# Power_Supply.net
KiCad netlist of a schematic drawn in Altium Designer
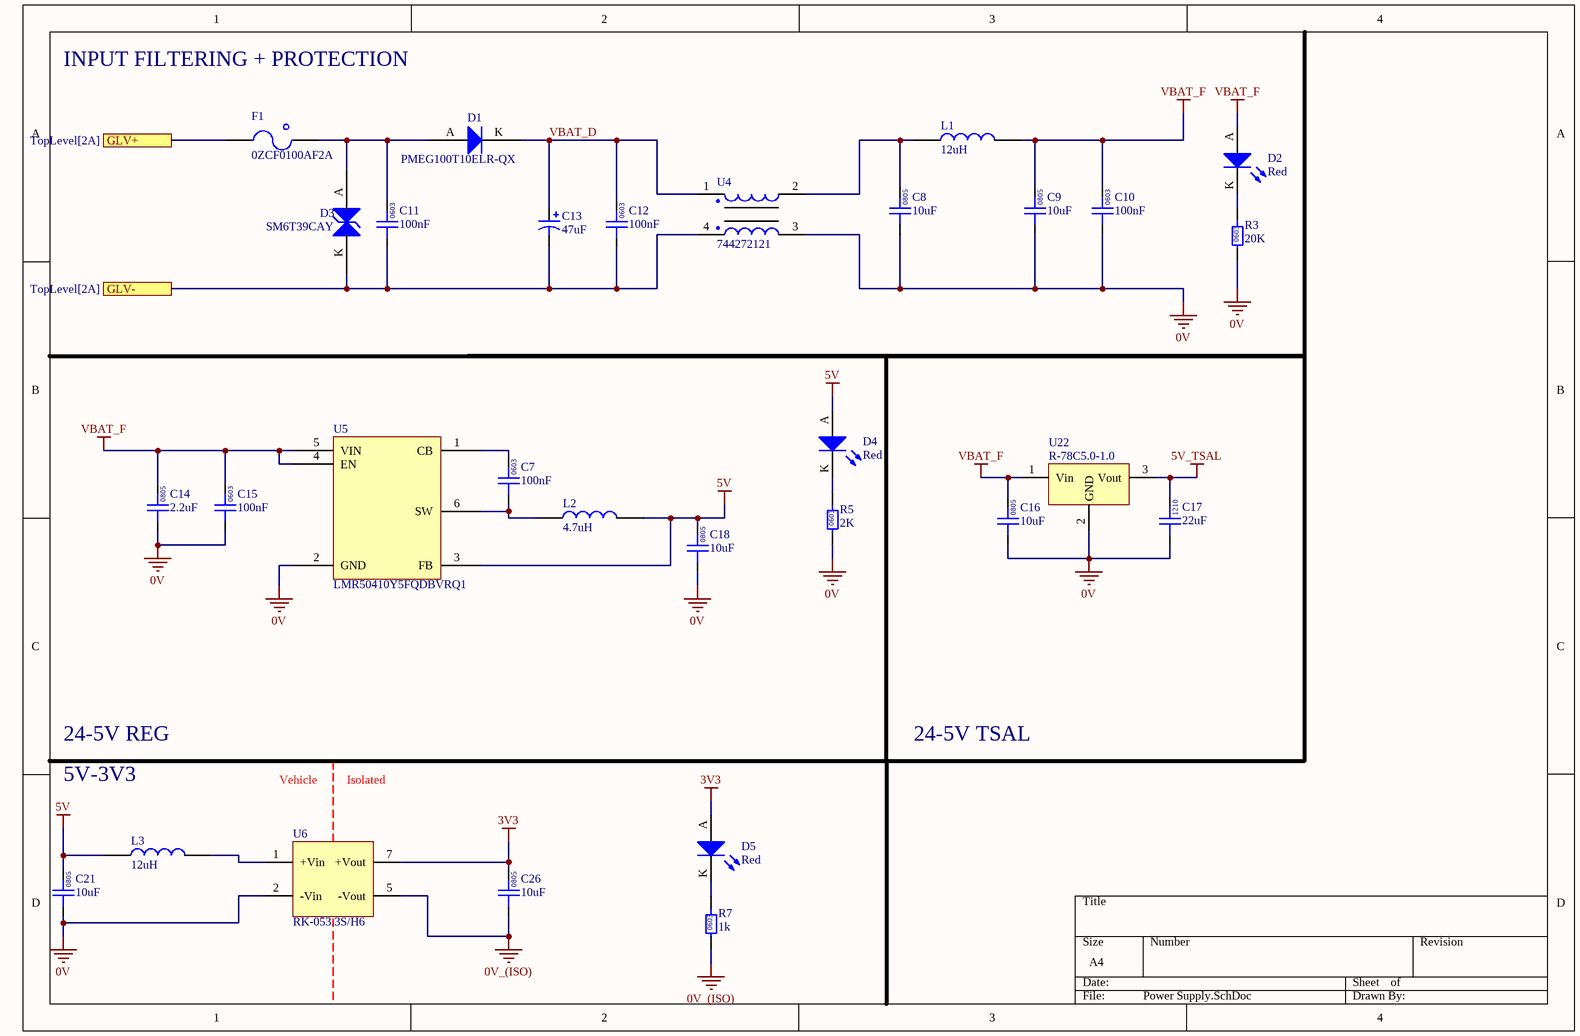
[diagram p0: Power Supply.SchDoc]

(export (version "E")
  (design (tool "Eeschema 10.0.6"))
  (components
    (comp (ref "C7")
      (value "100nF")
      (footprint "0603")
      (fields
        (field (name "PART NUMBER") "GCM188L81H104KA57D")
        (field (name "MANUFACTURER") "muRata")
        (field (name "TOLERANCE") "±10%")
      )
      (libsource (lib "ts_standard_library") (part "Capacitor 0603"))
    )
    (comp (ref "C8")
      (value "10uF")
      (footprint "0805")
      (fields
        (field (name "PART NUMBER") "GRM21BR6YA106KE43L")
        (field (name "MANUFACTURER") "muRata")
        (field (name "TOLERANCE") "10%")
      )
      (libsource (lib "ts_standard_library") (part "Capacitor 0805"))
    )
    (comp (ref "C9")
      (value "10uF")
      (footprint "0805")
      (fields
        (field (name "PART NUMBER") "GRM21BR6YA106KE43L")
        (field (name "MANUFACTURER") "muRata")
        (field (name "TOLERANCE") "10%")
      )
      (libsource (lib "ts_standard_library") (part "Capacitor 0805"))
    )
    (comp (ref "C10")
      (value "100nF")
      (footprint "0603")
      (fields
        (field (name "PART NUMBER") "GCM188L81H104KA57D")
        (field (name "MANUFACTURER") "muRata")
        (field (name "TOLERANCE") "±10%")
      )
      (libsource (lib "ts_standard_library") (part "Capacitor 0603"))
    )
    (comp (ref "C11")
      (value "100nF")
      (footprint "0603")
      (fields
        (field (name "PART NUMBER") "GCM188L81H104KA57D")
        (field (name "MANUFACTURER") "muRata")
        (field (name "TOLERANCE") "±10%")
      )
      (libsource (lib "ts_standard_library") (part "Capacitor 0603"))
    )
    (comp (ref "C12")
      (value "100nF")
      (footprint "0603")
      (fields
        (field (name "PART NUMBER") "GCM188L81H104KA57D")
        (field (name "MANUFACTURER") "muRata")
        (field (name "TOLERANCE") "±10%")
      )
      (libsource (lib "ts_standard_library") (part "Capacitor 0603"))
    )
    (comp (ref "C13")
      (value "47uF")
      (footprint "CHEMI-CON ELCO")
      (fields (field (name "PART NUMBER") "HHXA350ARA470MF61G"))
      (libsource (lib "ts_standard_library") (part "Capacitor (Polarised)"))
    )
    (comp (ref "C14")
      (value "2.2uF")
      (footprint "0805")
      (fields
        (field (name "PART NUMBER") "GRM21BR61A226ME51L")
        (field (name "MANUFACTURER") "muRata")
        (field (name "TOLERANCE") "20%")
      )
      (libsource (lib "ts_standard_library") (part "Capacitor 0805"))
    )
    (comp (ref "C15")
      (value "100nF")
      (footprint "0603")
      (fields
        (field (name "PART NUMBER") "GCM188L81H104KA57D")
        (field (name "MANUFACTURER") "muRata")
        (field (name "TOLERANCE") "±10%")
      )
      (libsource (lib "ts_standard_library") (part "Capacitor 0603"))
    )
    (comp (ref "C16")
      (value "10uF")
      (footprint "0805")
      (fields
        (field (name "PART NUMBER") "GRM21BR6YA106KE43L")
        (field (name "MANUFACTURER") "muRata")
        (field (name "TOLERANCE") "10%")
      )
      (libsource (lib "ts_standard_library") (part "Capacitor 0805"))
    )
    (comp (ref "C17")
      (value "22uF")
      (footprint "1210")
      (fields
        (field (name "PART NUMBER") "GRM32ER71E226KE15L")
        (field (name "MANUFACTURER") "Murata Electronics")
        (field (name "TOLERANCE") "±10%")
      )
      (libsource (lib "ts_standard_library") (part "Capacitor 1210"))
    )
    (comp (ref "C18")
      (value "10uF")
      (footprint "0805")
      (fields
        (field (name "PART NUMBER") "GRM21BR6YA106KE43L")
        (field (name "MANUFACTURER") "muRata")
        (field (name "TOLERANCE") "10%")
      )
      (libsource (lib "ts_standard_library") (part "Capacitor 0805"))
    )
    (comp (ref "C21")
      (value "10uF")
      (footprint "0805")
      (fields
        (field (name "PART NUMBER") "GRM21BR6YA106KE43L")
        (field (name "MANUFACTURER") "muRata")
        (field (name "TOLERANCE") "10%")
      )
      (libsource (lib "ts_standard_library") (part "Capacitor 0805"))
    )
    (comp (ref "C26")
      (value "10uF")
      (footprint "0805")
      (fields
        (field (name "PART NUMBER") "GRM21BR6YA106KE43L")
        (field (name "MANUFACTURER") "muRata")
        (field (name "TOLERANCE") "10%")
      )
      (libsource (lib "ts_standard_library") (part "Capacitor 0805"))
    )
    (comp (ref "D1")
      (value "PMEG100T10ELR-QX")
      (footprint "SODFL350X110-2N")
      (description "Diode 100 V 1A Surface Mount SOD-123W")
      (libsource (lib "Team Swinburne") (part "PMEG100T10ELR-QX"))
    )
    (comp (ref "D2")
      (value "Red")
      (footprint "0805 LED")
      (description "Red LED Indication - Discrete 1.75V 0805 (2012 Metric)")
      (fields (field (name "PART NUMBER") "SML-210LTT86") (field (name "MANUFACTURER") "ROHM Semiconductor"))
      (libsource (lib "ts_standard_library") (part "LED"))
    )
    (comp (ref "D3")
      (value "SM6T39CAY")
      (footprint "SM6T39CAY-Footprint-1")
      (description "TVS Diode Single Bi-Dir 33.3V 600W Automotive 2-Pin SMB T/R / TVS DIODE 33.3VWM 69.7VC SMB")
      (libsource (lib "Team Swinburne") (part "SM6T39CAY-Symbol"))
    )
    (comp (ref "D4")
      (value "Red")
      (footprint "0805 LED")
      (description "Red LED Indication - Discrete 1.75V 0805 (2012 Metric)")
      (fields (field (name "PART NUMBER") "SML-210LTT86") (field (name "MANUFACTURER") "ROHM Semiconductor"))
      (libsource (lib "ts_standard_library") (part "LED"))
    )
    (comp (ref "D5")
      (value "Red")
      (footprint "0805 LED")
      (description "Red LED Indication - Discrete 1.75V 0805 (2012 Metric)")
      (fields (field (name "PART NUMBER") "SML-210LTT86") (field (name "MANUFACTURER") "ROHM Semiconductor"))
      (libsource (lib "ts_standard_library") (part "LED"))
    )
    (comp (ref "F1")
      (value "0ZCF0100AF2A")
      (footprint "2920")
      (description "PTC RESET FUSE 60V 1A 292")
      (fields
        (field (name "MANUFACTURER") "Littelfuse Inc.")
        (field (name "DIGIKEY PART NUMBER") "507-2070-1-ND")
      )
      (libsource (lib "ts_standard_library") (part "PTC Fuse"))
    )
    (comp (ref "L1")
      (value "12uH")
      (footprint "1812")
      (fields
        (field (name "PART NUMBER") "RLS-126")
        (field (name "MANUFACTURER") "Recom")
        (field (name "TOLERANCE") "0.2")
      )
      (libsource (lib "ts_standard_library") (part "Inductor"))
    )
    (comp (ref "L2")
      (value "4.7uH")
      (footprint "SRN3015TA-4R7M")
      (fields
        (field (name "PART NUMBER") "SRN4018-4R7M")
        (field (name "MANUFACTURER") "Bourns")
        (field (name "TOLERANCE") "0.2")
      )
      (libsource (lib "ts_standard_library") (part "Inductor"))
    )
    (comp (ref "L3")
      (value "12uH")
      (footprint "1812")
      (fields
        (field (name "PART NUMBER") "RLS-126")
        (field (name "MANUFACTURER") "Recom")
        (field (name "TOLERANCE") "0.2")
      )
      (libsource (lib "ts_standard_library") (part "Inductor"))
    )
    (comp (ref "R3")
      (value "20K")
      (footprint "0603")
      (fields
        (field (name "PART NUMBER") "RC0603FR-0720KL")
        (field (name "MANUFACTURER") "YAGEO")
        (field (name "TOLERANCE") "0.01")
      )
      (libsource (lib "ts_standard_library") (part "Resistor 0603"))
    )
    (comp (ref "R5")
      (value "2K")
      (footprint "0603")
      (fields
        (field (name "PART NUMBER") "RC0603FR-072KL")
        (field (name "MANUFACTURER") "YAGEO")
        (field (name "TOLERANCE") "0.01")
      )
      (libsource (lib "ts_standard_library") (part "Resistor 0603"))
    )
    (comp (ref "R7")
      (value "1k")
      (footprint "0603")
      (fields
        (field (name "PART NUMBER") "RC0603FR-071KL")
        (field (name "MANUFACTURER") "YAGEO")
        (field (name "TOLERANCE") "0.01")
      )
      (libsource (lib "ts_standard_library") (part "Resistor 0603"))
    )
    (comp (ref "U4")
      (value "744272121")
      (footprint "Wurth 4-PC Pad")
      (fields
        (field (name "MANUFACTURER") "Wurth Electronics Inc")
        (field (name "DIGIKEY PART NUMBER") "732-1489-1-ND")
      )
      (libsource (lib "ts_standard_library") (part "CM Choke"))
    )
    (comp (ref "U5")
      (value "LMR50410Y5FQDBVRQ1")
      (footprint "TI-SOT23-6")
      (description "IC REG BUCK 5V 1A SOT23-6")
      (fields (field (name "PART NUMBER") "LMR50410-Q1") (field (name "MANUFACTURER") "Texas Instruments"))
      (libsource (lib "ts_standard_library") (part "LMR50410Y5FQDBVRQ1"))
    )
    (comp (ref "U6")
      (value "RK-053.3S/H6")
      (footprint "RK-053.3S/H6")
      (description "DC DC CONVERTER 3.3V 1W")
      (fields (field (name "MANUFACTURER") "Recom"))
      (libsource (lib "ts_standard_library") (part "RK-053.3S/H6"))
    )
    (comp (ref "U22")
      (value "R-78C5.0-1.0")
      (footprint "RECOM 3-SIP")
      (description "CONV DC/DC 1A 5V OUT SIP VERT")
      (fields (field (name "MANUFACTURER") "Recom") (field (name "DIGIKEY PART NUMBER") "945-1395-5-ND"))
      (libsource (lib "ts_20-standard-library") (part "R-78C5.0-1.0"))
    )
  )
  (nets
    (net (code "1") (name "/GLV+") (class "Default")
      (node (ref "F1") (pin "1") (pinfunction "1_1") (pintype "passive"))
    )
    (net (code "2") (name "/GLV-") (class "Default")
      (node (ref "C11") (pin "1") (pinfunction "1_1") (pintype "passive"))
      (node (ref "C12") (pin "1") (pinfunction "1_1") (pintype "passive"))
      (node (ref "C13") (pin "1") (pinfunction "1_1") (pintype "passive"))
      (node (ref "D3") (pin "K") (pintype "passive"))
      (node (ref "U4") (pin "4") (pinfunction "4_4") (pintype "passive"))
    )
    (net (code "3") (name "/VBAT_D") (class "Default")
      (node (ref "C12") (pin "2") (pinfunction "2_2") (pintype "passive"))
      (node (ref "C13") (pin "2") (pinfunction "2_2") (pintype "passive"))
      (node (ref "D1") (pin "K") (pintype "passive"))
      (node (ref "U4") (pin "1") (pinfunction "1_1") (pintype "passive"))
    )
    (net (code "4") (name "0V") (class "Default")
      (node (ref "C10") (pin "1") (pinfunction "1_1") (pintype "passive"))
      (node (ref "C14") (pin "1") (pinfunction "1_1") (pintype "passive"))
      (node (ref "C15") (pin "1") (pinfunction "1_1") (pintype "passive"))
      (node (ref "C16") (pin "1") (pinfunction "1_1") (pintype "passive"))
      (node (ref "C17") (pin "1") (pinfunction "1_1") (pintype "passive"))
      (node (ref "C18") (pin "1") (pinfunction "1_1") (pintype "passive"))
      (node (ref "C21") (pin "1") (pinfunction "1_1") (pintype "passive"))
      (node (ref "C8") (pin "1") (pinfunction "1_1") (pintype "passive"))
      (node (ref "C9") (pin "1") (pinfunction "1_1") (pintype "passive"))
      (node (ref "R3") (pin "1") (pinfunction "1_1") (pintype "passive"))
      (node (ref "R5") (pin "1") (pinfunction "1_1") (pintype "passive"))
      (node (ref "U22") (pin "2") (pinfunction "GND_2") (pintype "passive"))
      (node (ref "U4") (pin "3") (pinfunction "3_3") (pintype "power_in"))
      (node (ref "U5") (pin "2") (pinfunction "GND_2") (pintype "passive"))
      (node (ref "U6") (pin "2") (pinfunction "-Vin_2") (pintype "power_in"))
    )
    (net (code "5") (name "0V_(ISO)") (class "Default")
      (node (ref "C26") (pin "1") (pinfunction "1_1") (pintype "passive"))
      (node (ref "R7") (pin "1") (pinfunction "1_1") (pintype "passive"))
      (node (ref "U6") (pin "5") (pinfunction "-Vout_5") (pintype "power_in"))
    )
    (net (code "6") (name "3V3") (class "Default")
      (node (ref "C26") (pin "2") (pinfunction "2_2") (pintype "passive"))
      (node (ref "D5") (pin "A") (pinfunction "A_A") (pintype "passive"))
      (node (ref "U6") (pin "7") (pinfunction "+Vout_7") (pintype "power_in"))
    )
    (net (code "7") (name "5V") (class "Default")
      (node (ref "C18") (pin "2") (pinfunction "2_2") (pintype "passive"))
      (node (ref "C21") (pin "2") (pinfunction "2_2") (pintype "passive"))
      (node (ref "D4") (pin "A") (pinfunction "A_A") (pintype "passive"))
      (node (ref "L2") (pin "1") (pinfunction "1_1") (pintype "passive"))
      (node (ref "L3") (pin "2") (pinfunction "2_2") (pintype "passive"))
      (node (ref "U5") (pin "3") (pinfunction "FB_3") (pintype "passive"))
    )
    (net (code "8") (name "5V_TSAL") (class "Default")
      (node (ref "C17") (pin "2") (pinfunction "2_2") (pintype "passive"))
      (node (ref "U22") (pin "3") (pinfunction "Vout_3") (pintype "passive"))
    )
    (net (code "9") (name "Net-(C8-Pad2)") (class "Default")
      (node (ref "C8") (pin "2") (pinfunction "2_2") (pintype "passive"))
      (node (ref "L1") (pin "2") (pinfunction "2_2") (pintype "passive"))
      (node (ref "U4") (pin "2") (pinfunction "2_2") (pintype "passive"))
    )
    (net (code "10") (name "Net-(C11-Pad2)") (class "Default")
      (node (ref "C11") (pin "2") (pinfunction "2_2") (pintype "passive"))
      (node (ref "D1") (pin "A") (pintype "passive"))
      (node (ref "D3") (pin "A") (pintype "passive"))
      (node (ref "F1") (pin "2") (pinfunction "2_2") (pintype "passive"))
    )
    (net (code "11") (name "Net-(D2-PadK)") (class "Default")
      (node (ref "D2") (pin "K") (pinfunction "K_K") (pintype "passive"))
      (node (ref "R3") (pin "2") (pinfunction "2_2") (pintype "passive"))
    )
    (net (code "12") (name "Net-(D4-PadK)") (class "Default")
      (node (ref "D4") (pin "K") (pinfunction "K_K") (pintype "passive"))
      (node (ref "R5") (pin "2") (pinfunction "2_2") (pintype "passive"))
    )
    (net (code "13") (name "Net-(D5-PadK)") (class "Default")
      (node (ref "D5") (pin "K") (pinfunction "K_K") (pintype "passive"))
      (node (ref "R7") (pin "2") (pinfunction "2_2") (pintype "passive"))
    )
    (net (code "14") (name "Net-(U5-CB)") (class "Default")
      (node (ref "C7") (pin "2") (pinfunction "2_2") (pintype "passive"))
      (node (ref "U5") (pin "1") (pinfunction "CB_1") (pintype "passive"))
    )
    (net (code "15") (name "Net-(U5-SW)") (class "Default")
      (node (ref "C7") (pin "1") (pinfunction "1_1") (pintype "passive"))
      (node (ref "L2") (pin "2") (pinfunction "2_2") (pintype "passive"))
      (node (ref "U5") (pin "6") (pinfunction "SW_6") (pintype "passive"))
    )
    (net (code "16") (name "Net-(U6-+Vin)") (class "Default")
      (node (ref "L3") (pin "1") (pinfunction "1_1") (pintype "passive"))
      (node (ref "U6") (pin "1") (pinfunction "+Vin_1") (pintype "power_in"))
    )
    (net (code "17") (name "VBAT_F") (class "Default")
      (node (ref "C10") (pin "2") (pinfunction "2_2") (pintype "passive"))
      (node (ref "C14") (pin "2") (pinfunction "2_2") (pintype "passive"))
      (node (ref "C15") (pin "2") (pinfunction "2_2") (pintype "passive"))
      (node (ref "C16") (pin "2") (pinfunction "2_2") (pintype "passive"))
      (node (ref "C9") (pin "2") (pinfunction "2_2") (pintype "passive"))
      (node (ref "D2") (pin "A") (pinfunction "A_A") (pintype "passive"))
      (node (ref "L1") (pin "1") (pinfunction "1_1") (pintype "passive"))
      (node (ref "U22") (pin "1") (pinfunction "Vin_1") (pintype "passive"))
      (node (ref "U5") (pin "4") (pinfunction "EN_4") (pintype "passive"))
      (node (ref "U5") (pin "5") (pinfunction "VIN_5") (pintype "passive"))
    )
  )
)
